# CRAFT_E_Stop_AJefferson.net
KiCad netlist of a schematic drawn in Altium Designer
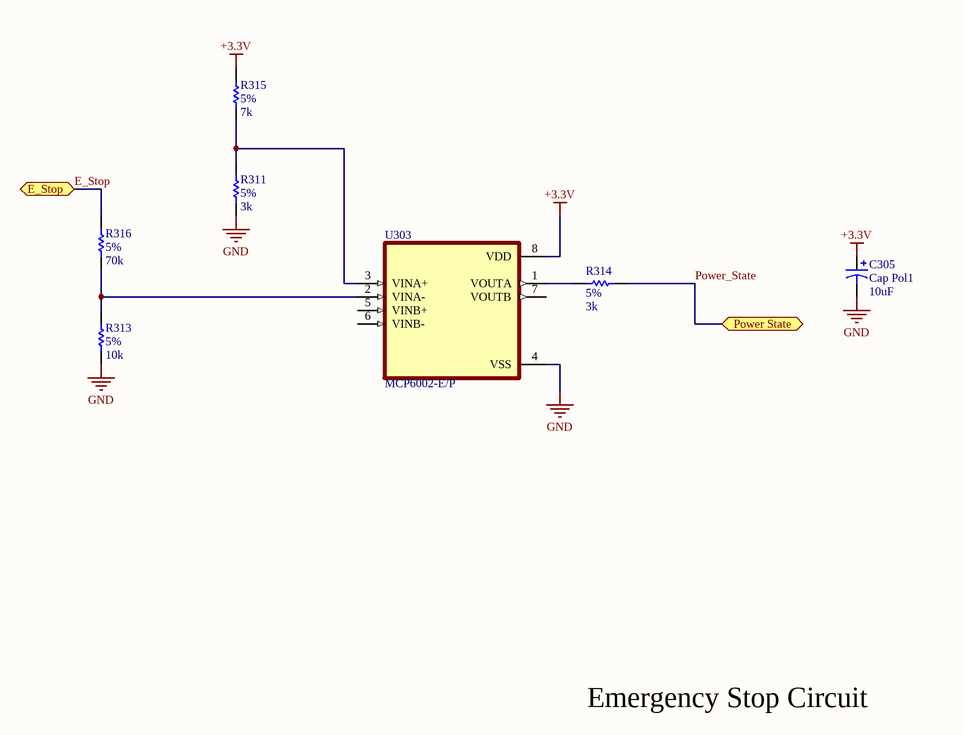
[diagram p0: CRAFT_E_Stop_AJefferson.SchDoc]

(export (version "E")
  (design (tool "Eeschema 10.0.6"))
  (components
    (comp (ref "C305")
      (value "Cap Pol1")
      (footprint "CAPPRD250W50D630H1120")
      (description "Polarized Capacitor (Radial)")
      (fields (field (name "ALTIUM_VALUE") "10uF") (field (name "PUBLISHER") "Altium Limited"))
      (libsource (lib "Miscellaneous Devices") (part "Cap Pol1"))
    )
    (comp (ref "R311")
      (value "5%")
      (footprint "AXIAL-0.3")
      (description "Resistor")
      (fields (field (name "ALTIUM_VALUE") "3k") (field (name "PUBLISHER") "Altium Limited"))
      (libsource (lib "Miscellaneous Devices") (part "Res1"))
    )
    (comp (ref "R313")
      (value "5%")
      (footprint "AXIAL-0.3")
      (description "Resistor")
      (fields (field (name "ALTIUM_VALUE") "10k") (field (name "PUBLISHER") "Altium Limited"))
      (libsource (lib "Miscellaneous Devices") (part "Res1"))
    )
    (comp (ref "R314")
      (value "5%")
      (footprint "AXIAL-0.3")
      (description "Resistor")
      (fields (field (name "ALTIUM_VALUE") "3k") (field (name "PUBLISHER") "Altium Limited"))
      (libsource (lib "Miscellaneous Devices") (part "Res1"))
    )
    (comp (ref "R315")
      (value "5%")
      (footprint "AXIAL-0.3")
      (description "Resistor")
      (fields (field (name "ALTIUM_VALUE") "7k") (field (name "PUBLISHER") "Altium Limited"))
      (libsource (lib "Miscellaneous Devices") (part "Res1"))
    )
    (comp (ref "R316")
      (value "5%")
      (footprint "AXIAL-0.3")
      (description "Resistor")
      (fields (field (name "ALTIUM_VALUE") "70k") (field (name "PUBLISHER") "Altium Limited"))
      (libsource (lib "Miscellaneous Devices") (part "Res1"))
    )
    (comp (ref "U303")
      (value "MCP6002-E/P")
      (footprint "DIP787W46P254L927H533Q8")
      (description "General Purpose Amplifier 2 Circuit Rail-to-Rail 8-PDIP")
      (fields (field (name "MF") "Microchip"))
      (libsource (lib "MCP6002-E_P") (part "MCP6002-E/P"))
    )
  )
  (nets
    (net (code "1") (name "+3.3V") (class "Default")
      (node (ref "C305") (pin "1") (pinfunction "1_1") (pintype "passive"))
      (node (ref "R315") (pin "2") (pinfunction "2_2") (pintype "passive"))
      (node (ref "U303") (pin "8") (pinfunction "VDD_8") (pintype "power_in"))
    )
    (net (code "2") (name "/E_Stop") (class "Default")
      (node (ref "R316") (pin "2") (pinfunction "2_2") (pintype "passive"))
    )
    (net (code "3") (name "/Power_State") (class "Default")
      (node (ref "R314") (pin "2") (pinfunction "2_2") (pintype "passive"))
    )
    (net (code "4") (name "GND") (class "Default")
      (node (ref "C305") (pin "2") (pinfunction "2_2") (pintype "passive"))
      (node (ref "R311") (pin "1") (pinfunction "1_1") (pintype "passive"))
      (node (ref "R313") (pin "1") (pinfunction "1_1") (pintype "passive"))
      (node (ref "U303") (pin "4") (pinfunction "VSS_4") (pintype "power_in"))
    )
    (net (code "5") (name "Net-(U303-VINA+)") (class "Default")
      (node (ref "R311") (pin "2") (pinfunction "2_2") (pintype "passive"))
      (node (ref "R315") (pin "1") (pinfunction "1_1") (pintype "passive"))
      (node (ref "U303") (pin "3") (pinfunction "VINA+_3") (pintype "input"))
    )
    (net (code "6") (name "Net-(U303-VINA-)") (class "Default")
      (node (ref "R313") (pin "2") (pinfunction "2_2") (pintype "passive"))
      (node (ref "R316") (pin "1") (pinfunction "1_1") (pintype "passive"))
      (node (ref "U303") (pin "2") (pinfunction "VINA-_2") (pintype "input"))
    )
    (net (code "7") (name "Net-(U303-VOUTA)") (class "Default")
      (node (ref "R314") (pin "1") (pinfunction "1_1") (pintype "passive"))
      (node (ref "U303") (pin "1") (pinfunction "VOUTA_1") (pintype "output"))
    )
    (net (code "8") (name "unconnected-(U303-VINB+-Pad5)") (class "Default")
      (node (ref "U303") (pin "5") (pinfunction "VINB+_5") (pintype "input"))
    )
    (net (code "9") (name "unconnected-(U303-VINB--Pad6)") (class "Default")
      (node (ref "U303") (pin "6") (pinfunction "VINB-_6") (pintype "input"))
    )
    (net (code "10") (name "unconnected-(U303-VOUTB-Pad7)") (class "Default")
      (node (ref "U303") (pin "7") (pinfunction "VOUTB_7") (pintype "output"))
    )
  )
)
